# USB_PORT_STACKED.net
KiCad netlist of a schematic drawn in Altium Designer
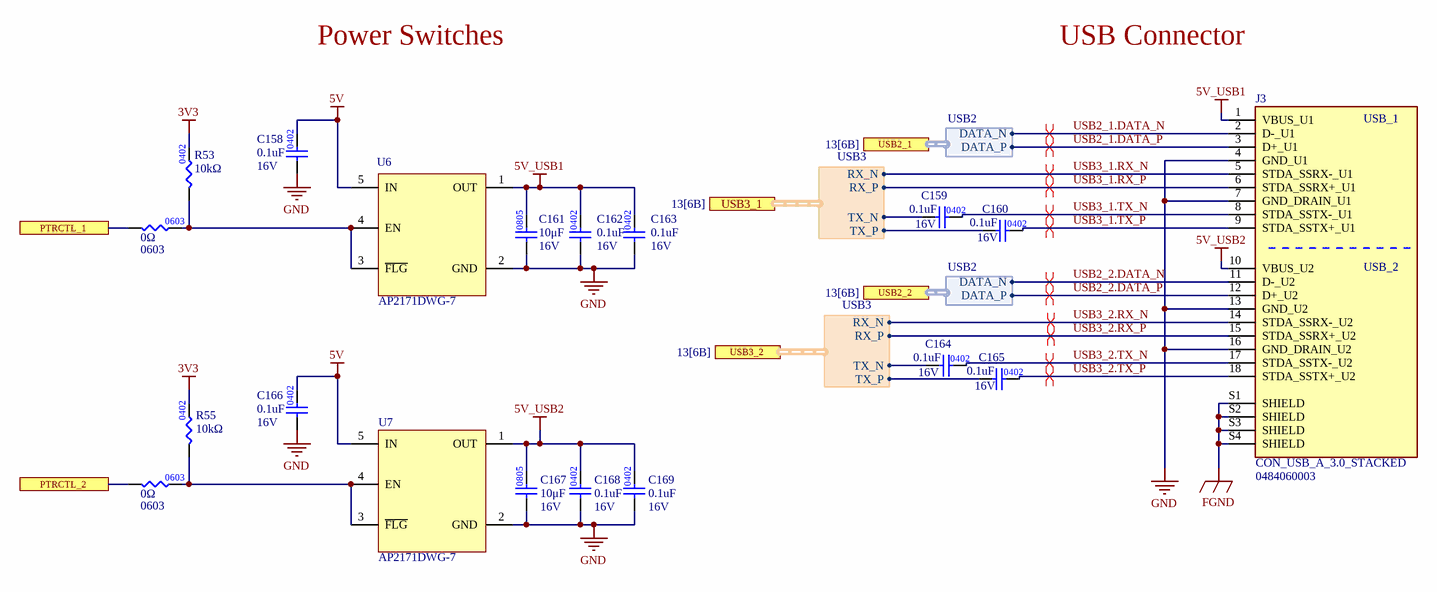
[diagram p0: USB PORT STACKED.SchDoc]

(export (version "E")
  (design (tool "Eeschema 10.0.6"))
  (components
    (comp (ref "C158")
      (value "CAP_0.1uF_16V_X7R_0402")
      (footprint "CAP0402")
      (description "Ceramic Capacitor, Ceramic")
      (fields
        (field (name "MANUFACTURER") "Taiyo Yuden")
        (field (name "MANUFACTURER PART NUMBER") "LMK212AC6106MD-T")
        (field (name "RATED DC VOLTAGE (URDC)") "16V")
        (field (name "CAPACITANCE") "0.1uF")
      )
      (libsource (lib "UWRT_Schematic_Library_2020") (part "CAP_0.1uF_16V_X7R_0402"))
    )
    (comp (ref "C159")
      (value "CAP_0.1uF_16V_X7R_0402")
      (footprint "CAP0402")
      (description "Ceramic Capacitor, Ceramic")
      (fields
        (field (name "CAPACITANCE") "0.1uF")
        (field (name "MANUFACTURER") "Taiyo Yuden")
        (field (name "MANUFACTURER PART NUMBER") "LMK212AC6106MD-T")
        (field (name "RATED DC VOLTAGE (URDC)") "16V")
      )
      (libsource (lib "UWRT_Schematic_Library_2020") (part "CAP_0.1uF_16V_X7R_0402"))
    )
    (comp (ref "C160")
      (value "CAP_0.1uF_16V_X7R_0402")
      (footprint "CAP0402")
      (description "Ceramic Capacitor, Ceramic")
      (fields
        (field (name "CAPACITANCE") "0.1uF")
        (field (name "MANUFACTURER") "Taiyo Yuden")
        (field (name "MANUFACTURER PART NUMBER") "LMK212AC6106MD-T")
        (field (name "RATED DC VOLTAGE (URDC)") "16V")
      )
      (libsource (lib "UWRT_Schematic_Library_2020") (part "CAP_0.1uF_16V_X7R_0402"))
    )
    (comp (ref "C161")
      (value "10μF")
      (footprint "CAP2012")
      (description "CAP CER 10UF 16V X5R 0805")
      (fields (field (name "VOLTAGE RATING") "16V") (field (name "Comment") "CAP_10uF_16V_0805"))
      (libsource (lib "UWRT_Schematic_Library_2020") (part "CAP_10uF_16V_0805"))
    )
    (comp (ref "C162")
      (value "CAP_0.1uF_16V_X7R_0402")
      (footprint "CAP0402")
      (description "Ceramic Capacitor, Ceramic")
      (fields
        (field (name "MANUFACTURER") "Taiyo Yuden")
        (field (name "MANUFACTURER PART NUMBER") "LMK212AC6106MD-T")
        (field (name "RATED DC VOLTAGE (URDC)") "16V")
        (field (name "CAPACITANCE") "0.1uF")
      )
      (libsource (lib "UWRT_Schematic_Library_2020") (part "CAP_0.1uF_16V_X7R_0402"))
    )
    (comp (ref "C163")
      (value "CAP_0.1uF_16V_X7R_0402")
      (footprint "CAP0402")
      (description "Ceramic Capacitor, Ceramic")
      (fields
        (field (name "MANUFACTURER") "Taiyo Yuden")
        (field (name "MANUFACTURER PART NUMBER") "LMK212AC6106MD-T")
        (field (name "RATED DC VOLTAGE (URDC)") "16V")
        (field (name "CAPACITANCE") "0.1uF")
      )
      (libsource (lib "UWRT_Schematic_Library_2020") (part "CAP_0.1uF_16V_X7R_0402"))
    )
    (comp (ref "C164")
      (value "CAP_0.1uF_16V_X7R_0402")
      (footprint "CAP0402")
      (description "Ceramic Capacitor, Ceramic")
      (fields
        (field (name "CAPACITANCE") "0.1uF")
        (field (name "MANUFACTURER") "Taiyo Yuden")
        (field (name "MANUFACTURER PART NUMBER") "LMK212AC6106MD-T")
        (field (name "RATED DC VOLTAGE (URDC)") "16V")
      )
      (libsource (lib "UWRT_Schematic_Library_2020") (part "CAP_0.1uF_16V_X7R_0402"))
    )
    (comp (ref "C165")
      (value "CAP_0.1uF_16V_X7R_0402")
      (footprint "CAP0402")
      (description "Ceramic Capacitor, Ceramic")
      (fields
        (field (name "CAPACITANCE") "0.1uF")
        (field (name "MANUFACTURER") "Taiyo Yuden")
        (field (name "MANUFACTURER PART NUMBER") "LMK212AC6106MD-T")
        (field (name "RATED DC VOLTAGE (URDC)") "16V")
      )
      (libsource (lib "UWRT_Schematic_Library_2020") (part "CAP_0.1uF_16V_X7R_0402"))
    )
    (comp (ref "C166")
      (value "CAP_0.1uF_16V_X7R_0402")
      (footprint "CAP0402")
      (description "Ceramic Capacitor, Ceramic")
      (fields
        (field (name "MANUFACTURER") "Taiyo Yuden")
        (field (name "MANUFACTURER PART NUMBER") "LMK212AC6106MD-T")
        (field (name "RATED DC VOLTAGE (URDC)") "16V")
        (field (name "CAPACITANCE") "0.1uF")
      )
      (libsource (lib "UWRT_Schematic_Library_2020") (part "CAP_0.1uF_16V_X7R_0402"))
    )
    (comp (ref "C167")
      (value "10μF")
      (footprint "CAP2012")
      (description "CAP CER 10UF 16V X5R 0805")
      (fields (field (name "VOLTAGE RATING") "16V") (field (name "Comment") "CAP_10uF_16V_0805"))
      (libsource (lib "UWRT_Schematic_Library_2020") (part "CAP_10uF_16V_0805"))
    )
    (comp (ref "C168")
      (value "CAP_0.1uF_16V_X7R_0402")
      (footprint "CAP0402")
      (description "Ceramic Capacitor, Ceramic")
      (fields
        (field (name "MANUFACTURER") "Taiyo Yuden")
        (field (name "MANUFACTURER PART NUMBER") "LMK212AC6106MD-T")
        (field (name "RATED DC VOLTAGE (URDC)") "16V")
        (field (name "CAPACITANCE") "0.1uF")
      )
      (libsource (lib "UWRT_Schematic_Library_2020") (part "CAP_0.1uF_16V_X7R_0402"))
    )
    (comp (ref "C169")
      (value "CAP_0.1uF_16V_X7R_0402")
      (footprint "CAP0402")
      (description "Ceramic Capacitor, Ceramic")
      (fields
        (field (name "MANUFACTURER") "Taiyo Yuden")
        (field (name "MANUFACTURER PART NUMBER") "LMK212AC6106MD-T")
        (field (name "RATED DC VOLTAGE (URDC)") "16V")
        (field (name "CAPACITANCE") "0.1uF")
      )
      (libsource (lib "UWRT_Schematic_Library_2020") (part "CAP_0.1uF_16V_X7R_0402"))
    )
    (comp (ref "J3")
      (value "CON_USB_A_3.0_STACKED")
      (footprint "MOLEX_0484060003")
      (description "CONN RCPT USB3.0 TYPEA STACK R/A")
      (fields (field (name "MANUFACTURER PART NUMBER 1") "0484060003"))
      (libsource (lib "UWRT_Schematic_Library_2020") (part "CON_USB_A_3.0_STACKED"))
    )
    (comp (ref "R53")
      (value "10kΩ")
      (footprint "RES0402")
      (description "RES SMD 10K OHM 1% 1/16W 0402")
      (fields (field (name "POWER") "0.063W, 1/16W") (field (name "TOLERANCE") "1%"))
      (libsource (lib "UWRT_Schematic_Library_2020") (part "RES_10kΩ_0402_1%"))
    )
    (comp (ref "R54")
      (value "0Ω")
      (footprint "RES0603")
      (description "RES 0 OHM JUMPER 1/10W 0603")
      (fields (field (name "PACKAGE/FOOTPRINT") "0603") (field (name "Comment") "RES_0Ω_0603"))
      (libsource (lib "UWRT_Schematic_Library_2020") (part "RES_0Ω_0603"))
    )
    (comp (ref "R55")
      (value "10kΩ")
      (footprint "RES0402")
      (description "RES SMD 10K OHM 1% 1/16W 0402")
      (fields (field (name "POWER") "0.063W, 1/16W") (field (name "TOLERANCE") "1%"))
      (libsource (lib "UWRT_Schematic_Library_2020") (part "RES_10kΩ_0402_1%"))
    )
    (comp (ref "R56")
      (value "0Ω")
      (footprint "RES0603")
      (description "RES 0 OHM JUMPER 1/10W 0603")
      (fields (field (name "PACKAGE/FOOTPRINT") "0603") (field (name "Comment") "RES_0Ω_0603"))
      (libsource (lib "UWRT_Schematic_Library_2020") (part "RES_0Ω_0603"))
    )
    (comp (ref "U6")
      (value "AP2171DWG-7")
      (footprint "AP2171DWG-7")
      (description "IC PWR SWITCH P-CHAN 1:1 SOT25")
      (libsource (lib "UWRT_Schematic_Library_2020") (part "AP2171DWG-7"))
    )
    (comp (ref "U7")
      (value "AP2171DWG-7")
      (footprint "AP2171DWG-7")
      (description "IC PWR SWITCH P-CHAN 1:1 SOT25")
      (libsource (lib "UWRT_Schematic_Library_2020") (part "AP2171DWG-7"))
    )
  )
  (nets
    (net (code "3") (name "/PTRCTL_1") (class "Default")
      (node (ref "R54") (pin "1") (pinfunction "1_1") (pintype "passive"))
    )
    (net (code "4") (name "/PTRCTL_2") (class "Default")
      (node (ref "R56") (pin "1") (pinfunction "1_1") (pintype "passive"))
    )
    (net (code "5") (name "/USB2_1.DATA_N") (class "Default")
      (node (ref "J3") (pin "2") (pinfunction "D-_U1_2") (pintype "passive"))
    )
    (net (code "6") (name "/USB2_1.DATA_P") (class "Default")
      (node (ref "J3") (pin "3") (pinfunction "D+_U1_3") (pintype "passive"))
    )
    (net (code "7") (name "/USB2_2.DATA_N") (class "Default")
      (node (ref "J3") (pin "11") (pinfunction "D-_U2_11") (pintype "passive"))
    )
    (net (code "8") (name "/USB2_2.DATA_P") (class "Default")
      (node (ref "J3") (pin "12") (pinfunction "D+_U2_12") (pintype "passive"))
    )
    (net (code "9") (name "/USB3_1.RX_N") (class "Default")
      (node (ref "J3") (pin "5") (pinfunction "STDA_SSRX-_U1_5") (pintype "passive"))
    )
    (net (code "10") (name "/USB3_1.RX_P") (class "Default")
      (node (ref "J3") (pin "6") (pinfunction "STDA_SSRX+_U1_6") (pintype "passive"))
    )
    (net (code "11") (name "/USB3_1.TX_N") (class "Default")
      (node (ref "C159") (pin "2") (pinfunction "2_2") (pintype "passive"))
      (node (ref "J3") (pin "8") (pinfunction "STDA_SSTX-_U1_8") (pintype "passive"))
    )
    (net (code "12") (name "/USB3_1.TX_P") (class "Default")
      (node (ref "C160") (pin "2") (pinfunction "2_2") (pintype "passive"))
      (node (ref "J3") (pin "9") (pinfunction "STDA_SSTX+_U1_9") (pintype "passive"))
    )
    (net (code "13") (name "/USB3_2.RX_N") (class "Default")
      (node (ref "J3") (pin "14") (pinfunction "STDA_SSRX-_U2_14") (pintype "passive"))
    )
    (net (code "14") (name "/USB3_2.RX_P") (class "Default")
      (node (ref "J3") (pin "15") (pinfunction "STDA_SSRX+_U2_15") (pintype "passive"))
    )
    (net (code "15") (name "/USB3_2.TX_N") (class "Default")
      (node (ref "C164") (pin "2") (pinfunction "2_2") (pintype "passive"))
      (node (ref "J3") (pin "17") (pinfunction "STDA_SSTX-_U2_17") (pintype "passive"))
    )
    (net (code "16") (name "/USB3_2.TX_P") (class "Default")
      (node (ref "C165") (pin "2") (pinfunction "2_2") (pintype "passive"))
      (node (ref "J3") (pin "18") (pinfunction "STDA_SSTX+_U2_18") (pintype "passive"))
    )
    (net (code "19") (name "3V3") (class "Default")
      (node (ref "R53") (pin "2") (pinfunction "2_2") (pintype "passive"))
      (node (ref "R55") (pin "2") (pinfunction "2_2") (pintype "passive"))
    )
    (net (code "20") (name "5V") (class "Default")
      (node (ref "C158") (pin "2") (pinfunction "2_2") (pintype "passive"))
      (node (ref "C166") (pin "2") (pinfunction "2_2") (pintype "passive"))
      (node (ref "U6") (pin "5") (pinfunction "IN_5") (pintype "passive"))
      (node (ref "U7") (pin "5") (pinfunction "IN_5") (pintype "passive"))
    )
    (net (code "21") (name "5V_USB1") (class "Default")
      (node (ref "C161") (pin "2") (pinfunction "2_2") (pintype "passive"))
      (node (ref "C162") (pin "2") (pinfunction "2_2") (pintype "passive"))
      (node (ref "C163") (pin "2") (pinfunction "2_2") (pintype "passive"))
      (node (ref "J3") (pin "1") (pinfunction "VBUS_U1_1") (pintype "passive"))
      (node (ref "U6") (pin "1") (pinfunction "OUT_1") (pintype "passive"))
    )
    (net (code "22") (name "5V_USB2") (class "Default")
      (node (ref "C167") (pin "2") (pinfunction "2_2") (pintype "passive"))
      (node (ref "C168") (pin "2") (pinfunction "2_2") (pintype "passive"))
      (node (ref "C169") (pin "2") (pinfunction "2_2") (pintype "passive"))
      (node (ref "J3") (pin "10") (pinfunction "VBUS_U2_10") (pintype "passive"))
      (node (ref "U7") (pin "1") (pinfunction "OUT_1") (pintype "passive"))
    )
    (net (code "23") (name "FGND") (class "Default")
      (node (ref "J3") (pin "S1") (pinfunction "SHIELD_S1") (pintype "passive"))
      (node (ref "J3") (pin "S2") (pinfunction "SHIELD_S2") (pintype "passive"))
      (node (ref "J3") (pin "S3") (pinfunction "SHIELD_S3") (pintype "passive"))
      (node (ref "J3") (pin "S4") (pinfunction "SHIELD_S4") (pintype "passive"))
    )
    (net (code "24") (name "GND") (class "Default")
      (node (ref "C158") (pin "1") (pinfunction "1_1") (pintype "passive"))
      (node (ref "C161") (pin "1") (pinfunction "1_1") (pintype "passive"))
      (node (ref "C162") (pin "1") (pinfunction "1_1") (pintype "passive"))
      (node (ref "C163") (pin "1") (pinfunction "1_1") (pintype "passive"))
      (node (ref "C166") (pin "1") (pinfunction "1_1") (pintype "passive"))
      (node (ref "C167") (pin "1") (pinfunction "1_1") (pintype "passive"))
      (node (ref "C168") (pin "1") (pinfunction "1_1") (pintype "passive"))
      (node (ref "C169") (pin "1") (pinfunction "1_1") (pintype "passive"))
      (node (ref "J3") (pin "13") (pinfunction "GND_U2_13") (pintype "passive"))
      (node (ref "J3") (pin "16") (pinfunction "GND_DRAIN_U2_16") (pintype "passive"))
      (node (ref "J3") (pin "4") (pinfunction "GND_U1_4") (pintype "passive"))
      (node (ref "J3") (pin "7") (pinfunction "GND_DRAIN_U1_7") (pintype "passive"))
      (node (ref "U6") (pin "2") (pinfunction "GND_2") (pintype "passive"))
      (node (ref "U7") (pin "2") (pinfunction "GND_2") (pintype "passive"))
    )
    (net (code "25") (name "Net-(U6-EN)") (class "Default")
      (node (ref "R53") (pin "1") (pinfunction "1_1") (pintype "passive"))
      (node (ref "R54") (pin "2") (pinfunction "2_2") (pintype "passive"))
      (node (ref "U6") (pin "3") (pinfunction "~{FLG}_3") (pintype "passive"))
      (node (ref "U6") (pin "4") (pinfunction "EN_4") (pintype "passive"))
    )
    (net (code "26") (name "Net-(U7-EN)") (class "Default")
      (node (ref "R55") (pin "1") (pinfunction "1_1") (pintype "passive"))
      (node (ref "R56") (pin "2") (pinfunction "2_2") (pintype "passive"))
      (node (ref "U7") (pin "3") (pinfunction "~{FLG}_3") (pintype "passive"))
      (node (ref "U7") (pin "4") (pinfunction "EN_4") (pintype "passive"))
    )
    (net (code "27") (name "unconnected-(C159-Pad1)") (class "Default")
      (node (ref "C159") (pin "1") (pinfunction "1_1") (pintype "passive"))
    )
    (net (code "28") (name "unconnected-(C160-Pad1)") (class "Default")
      (node (ref "C160") (pin "1") (pinfunction "1_1") (pintype "passive"))
    )
    (net (code "29") (name "unconnected-(C164-Pad1)") (class "Default")
      (node (ref "C164") (pin "1") (pinfunction "1_1") (pintype "passive"))
    )
    (net (code "30") (name "unconnected-(C165-Pad1)") (class "Default")
      (node (ref "C165") (pin "1") (pinfunction "1_1") (pintype "passive"))
    )
  )
)
